# Ada.net
KiCad netlist of a schematic drawn in EasyEDA Pro
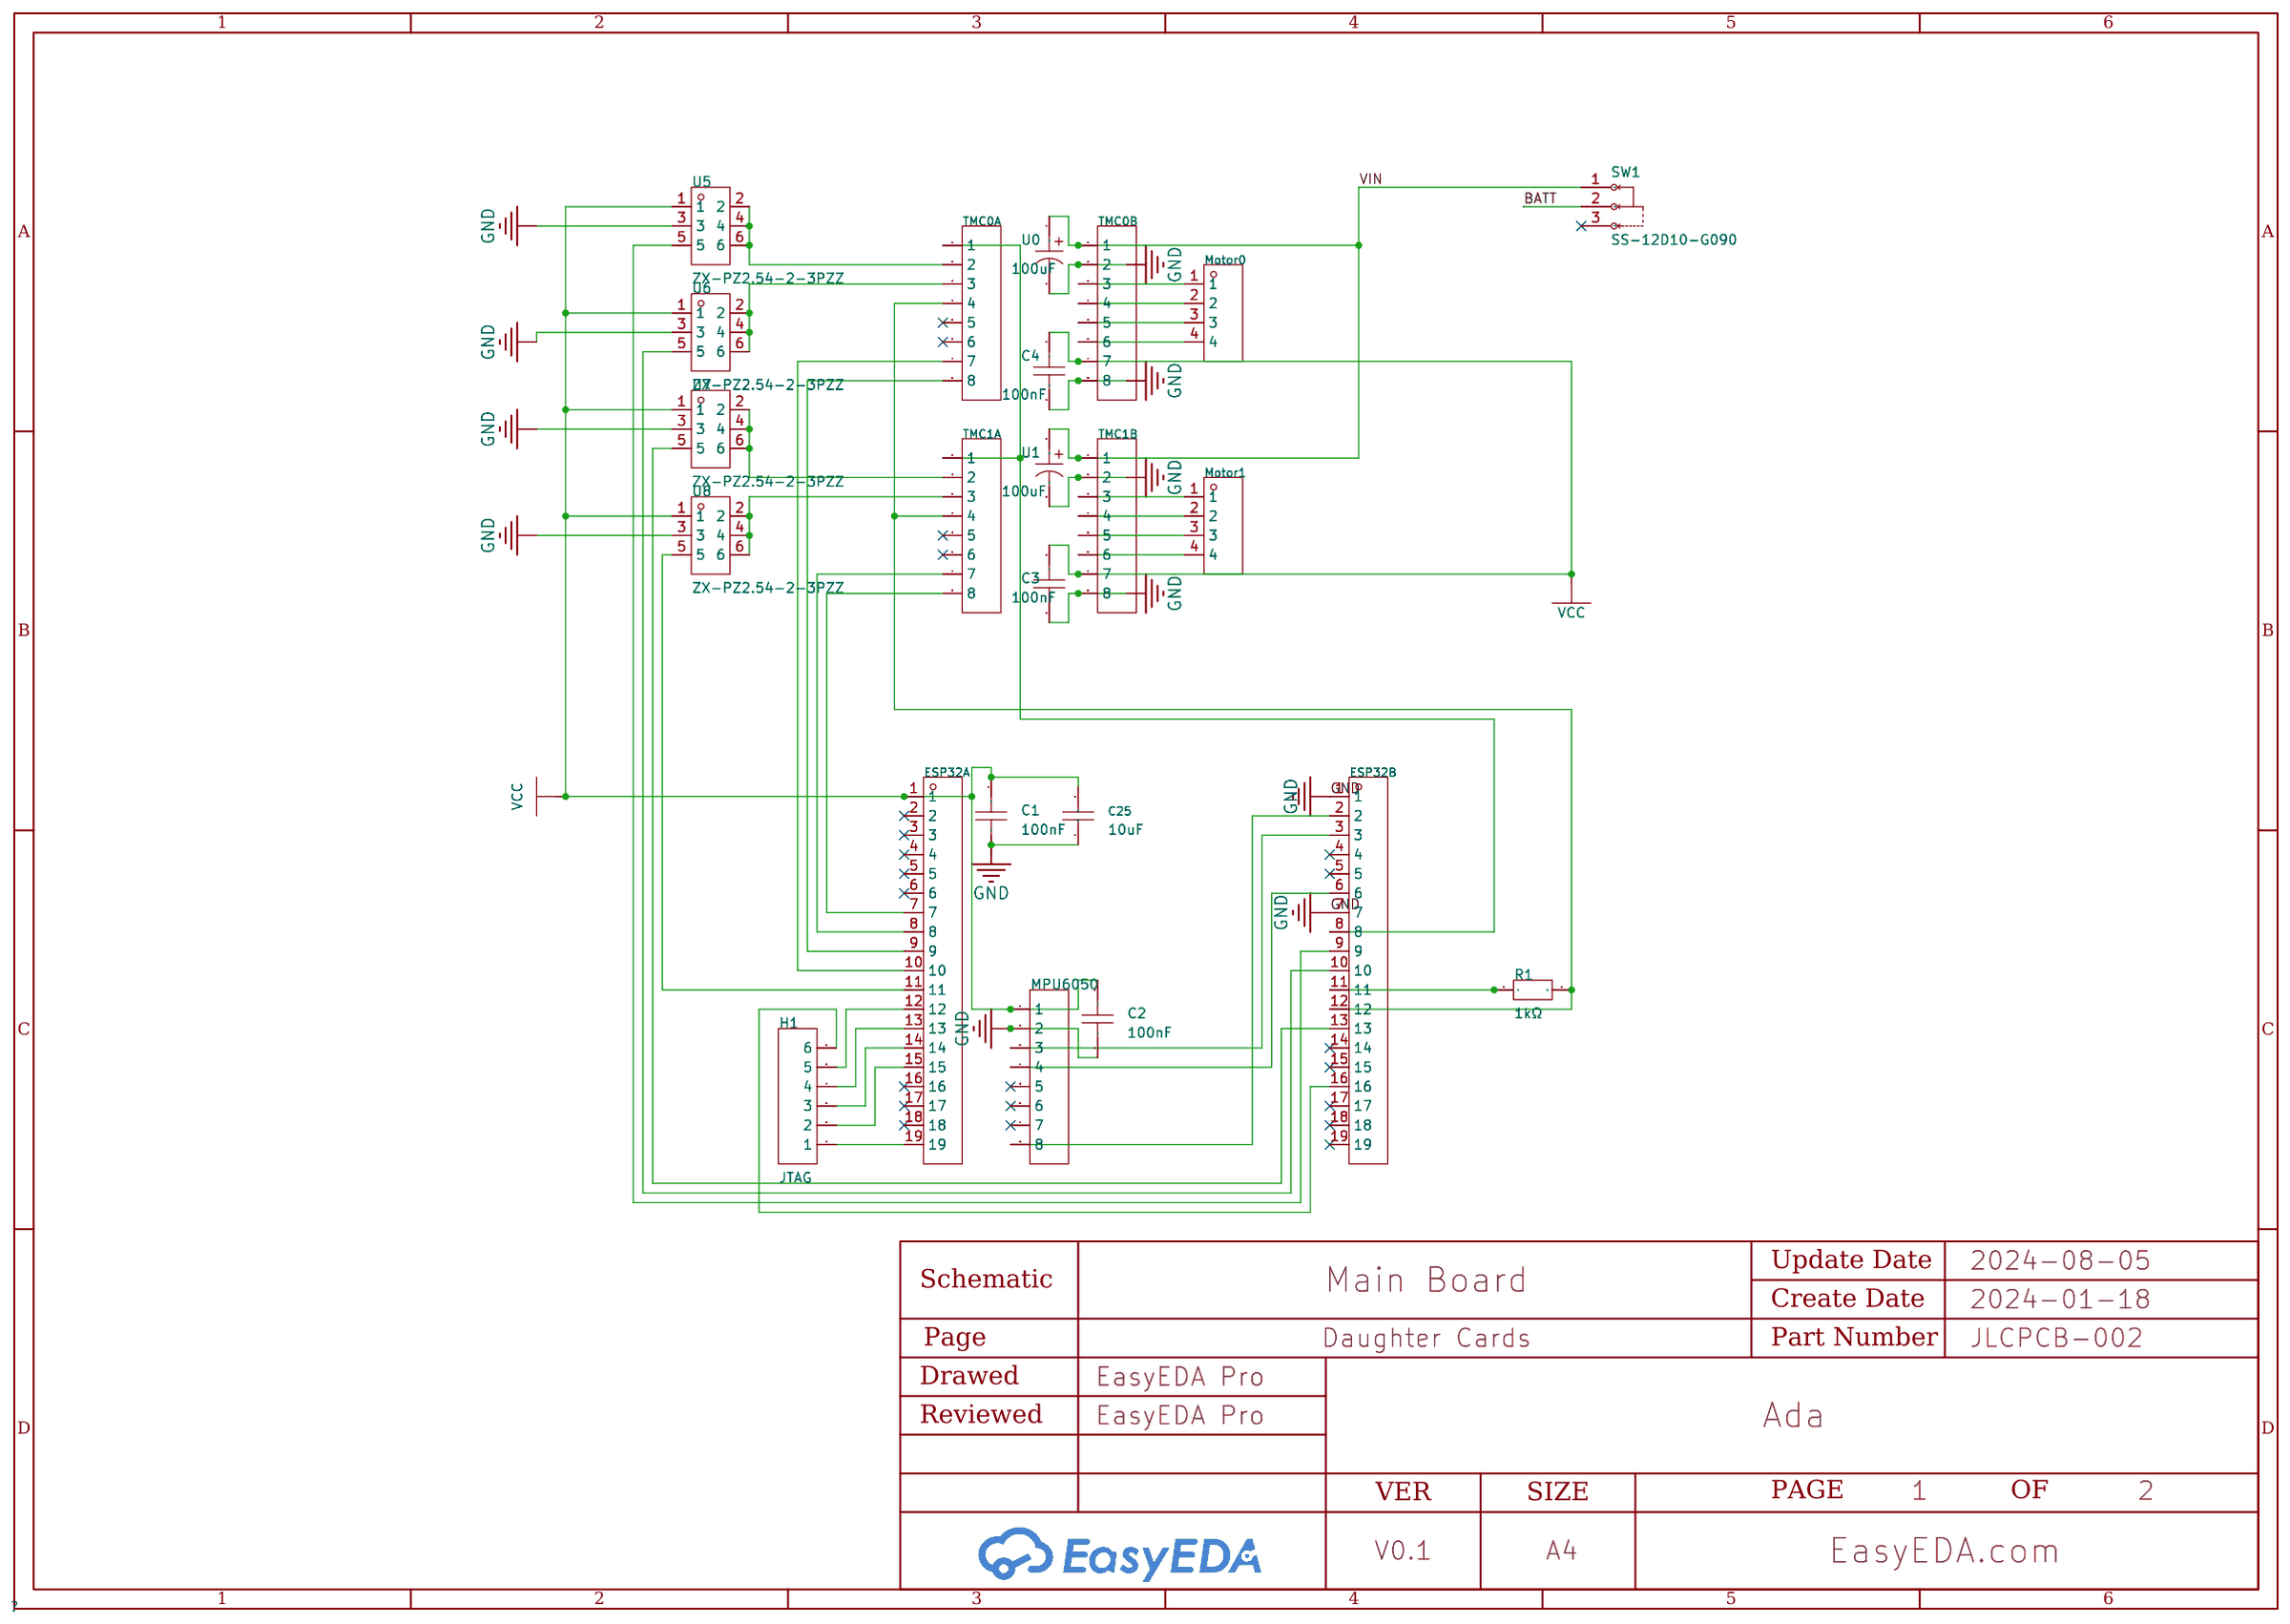
[diagram p0: Daughter Cards]
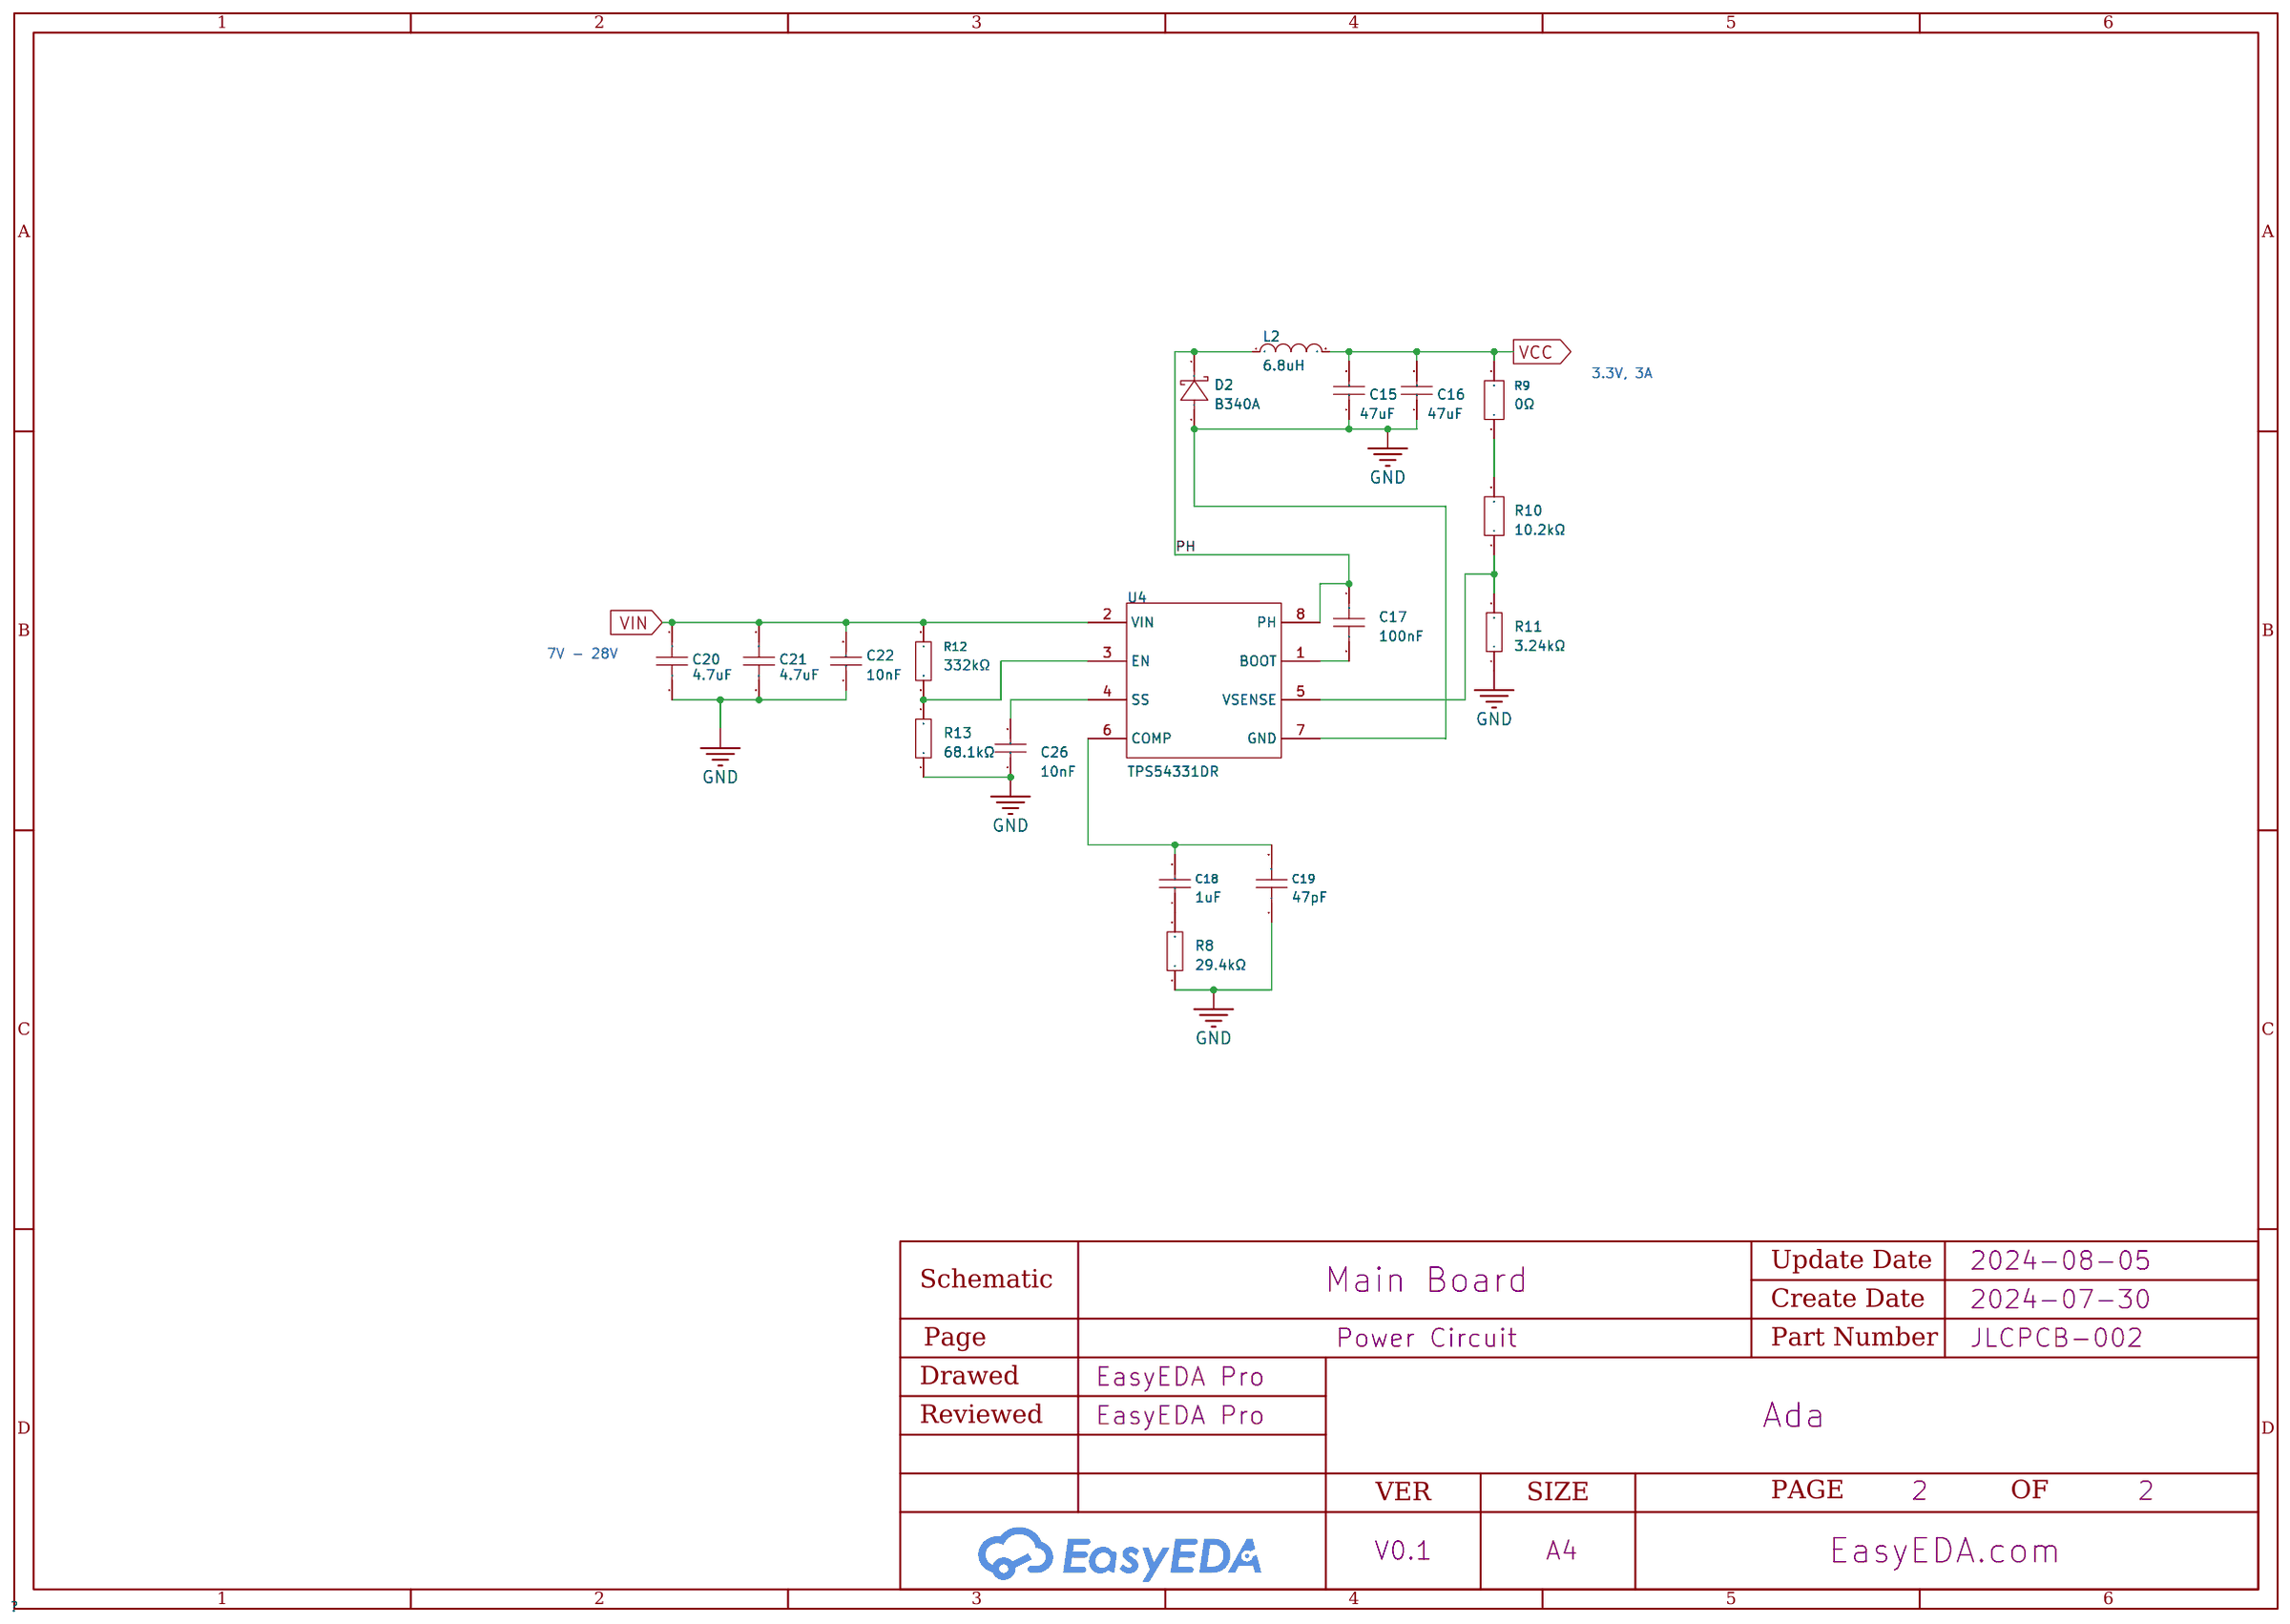
[diagram p1: Power Circuit]

(export (version "E")
  (design (tool "Eeschema 10.0.6"))
  (components
    (comp (ref "C1")
      (value "100nF")
      (footprint "easyedapro:C0201")
      (fields
        (field (name "Manufacturer Part") "CL03A104KQ3NNNC")
        (field (name "Manufacturer") "SAMSUNG(三星)")
      )
      (libsource (lib "easyedapro") (part "CL03A104KQ3NNNC"))
    )
    (comp (ref "C2")
      (value "100nF")
      (footprint "easyedapro:C0201")
      (fields
        (field (name "Manufacturer Part") "CL03A104KQ3NNNC")
        (field (name "Manufacturer") "SAMSUNG(三星)")
      )
      (libsource (lib "easyedapro") (part "CL03A104KQ3NNNC"))
    )
    (comp (ref "C3")
      (value "100nF")
      (footprint "easyedapro:C0201")
      (fields
        (field (name "Manufacturer Part") "CL03A104KQ3NNNC")
        (field (name "Manufacturer") "SAMSUNG(三星)")
      )
      (libsource (lib "easyedapro") (part "CL03A104KQ3NNNC"))
    )
    (comp (ref "C4")
      (value "100nF")
      (footprint "easyedapro:C0201")
      (fields
        (field (name "Manufacturer Part") "CL03A104KQ3NNNC")
        (field (name "Manufacturer") "SAMSUNG(三星)")
      )
      (libsource (lib "easyedapro") (part "CL03A104KQ3NNNC"))
    )
    (comp (ref "C25")
      (value "10uF")
      (footprint "easyedapro:C0402")
      (fields
        (field (name "Manufacturer Part") "CL05A106MQ5NUNC")
        (field (name "Manufacturer") "SAMSUNG(三星)")
      )
      (libsource (lib "easyedapro") (part "CL05A106MQ5NUNC"))
    )
    (comp (ref "ESP32A")
      (value "ESP32")
      (footprint "easyedapro:HDR-TH_19P-P2.54-V-F")
      (fields (field (name "Manufacturer Part") "2.54-1*19P母") (field (name "Manufacturer") "BOOMELE(博穆精密)"))
      (libsource (lib "easyedapro") (part "2.54-1*19P母"))
    )
    (comp (ref "ESP32B")
      (value "2.54-1*19P母")
      (footprint "easyedapro:HDR-TH_19P-P2.54-V-F")
      (fields (field (name "Manufacturer") "BOOMELE(博穆精密)"))
      (libsource (lib "easyedapro") (part "2.54-1*19P母"))
    )
    (comp (ref "H1")
      (value "JTAG")
      (footprint "easyedapro:HDR-TH_6P-P2.54-V-M-1")
      (fields (field (name "Manufacturer Part") "2.54-1x6P直针") (field (name "Manufacturer") "BOOMELE(博穆精密)"))
      (libsource (lib "easyedapro") (part "Header-Male-2.54_1x6"))
    )
    (comp (ref "Motor0")
      (value "Motor 0")
      (footprint "easyedapro:HDR-TH_4P-P2.54-V-M")
      (fields (field (name "Manufacturer Part") "PZ254V-11-04P") (field (name "Manufacturer") "XFCN(兴飞)"))
      (libsource (lib "easyedapro") (part "PZ254V-11-04P_C2691448"))
    )
    (comp (ref "Motor1")
      (value "Motor 1")
      (footprint "easyedapro:HDR-TH_4P-P2.54-V-M")
      (fields (field (name "Manufacturer Part") "PZ254V-11-04P") (field (name "Manufacturer") "XFCN(兴飞)"))
      (libsource (lib "easyedapro") (part "PZ254V-11-04P_C2691448"))
    )
    (comp (ref "MPU6050")
      (value "MPU6050")
      (footprint "easyedapro:HDR-TH_8P-P2.54-V-F-1")
      (fields (field (name "Manufacturer Part") "2.54-1*8P母环保") (field (name "Manufacturer") "BOOMELE(博穆精密)"))
      (libsource (lib "easyedapro") (part "Header-Female-2.54_1x8"))
    )
    (comp (ref "R1")
      (value "1kΩ")
      (footprint "easyedapro:R0603")
      (fields (field (name "Manufacturer Part") "FCR0603F1K") (field (name "Manufacturer") "VO(翔胜)"))
      (libsource (lib "easyedapro") (part "FCR0603F1K"))
    )
    (comp (ref "SW1")
      (value "SS-12D10-G090")
      (footprint "easyedapro:SW-TH_3P-L12.7-W6.6-P4.70_C9900034369")
      (fields (field (name "Manufacturer") "G-Switch(品赞)"))
      (libsource (lib "easyedapro") (part "SS-12D10-G090"))
    )
    (comp (ref "TMC0A")
      (value "TMC0A")
      (footprint "easyedapro:HDR-TH_8P-P2.54-V-F-1")
      (fields (field (name "Manufacturer Part") "2.54-1*8P母环保") (field (name "Manufacturer") "BOOMELE(博穆精密)"))
      (libsource (lib "easyedapro") (part "Header-Female-2.54_1x8"))
    )
    (comp (ref "TMC0B")
      (value "2.54-1*8P母环保")
      (footprint "easyedapro:HDR-TH_8P-P2.54-V-F-1")
      (fields (field (name "Manufacturer") "BOOMELE(博穆精密)"))
      (libsource (lib "easyedapro") (part "Header-Female-2.54_1x8"))
    )
    (comp (ref "TMC1A")
      (value "TMC2209")
      (footprint "easyedapro:HDR-TH_8P-P2.54-V-F-1")
      (fields (field (name "Manufacturer Part") "2.54-1*8P母环保") (field (name "Manufacturer") "BOOMELE(博穆精密)"))
      (libsource (lib "easyedapro") (part "Header-Female-2.54_1x8"))
    )
    (comp (ref "TMC1B")
      (value "2.54-1*8P母环保")
      (footprint "easyedapro:HDR-TH_8P-P2.54-V-F-1")
      (fields (field (name "Manufacturer") "BOOMELE(博穆精密)"))
      (libsource (lib "easyedapro") (part "Header-Female-2.54_1x8"))
    )
    (comp (ref "U0")
      (value "100uF")
      (footprint "easyedapro:CAP-TH_BD6.3-P2.50-D0.5-FD")
      (fields (field (name "Manufacturer Part") "03EC0728") (field (name "Manufacturer") "KNSCHA(科尼盛)"))
      (libsource (lib "easyedapro") (part "03EC0728"))
    )
    (comp (ref "U1")
      (value "100uF")
      (footprint "easyedapro:CAP-TH_BD6.3-P2.50-D0.5-FD")
      (fields (field (name "Manufacturer Part") "03EC0728") (field (name "Manufacturer") "KNSCHA(科尼盛)"))
      (libsource (lib "easyedapro") (part "03EC0728"))
    )
    (comp (ref "U5")
      (value "ZX-PZ2.54-2-3PZZ")
      (footprint "easyedapro:HDR-TH_6P-P2.54-V-M-R2-C3-S2.54-1")
      (fields (field (name "Manufacturer") "Megastar(兆星)"))
      (libsource (lib "easyedapro") (part "ZX-PZ2.54-2-3PZZ"))
    )
    (comp (ref "U6")
      (value "ZX-PZ2.54-2-3PZZ")
      (footprint "easyedapro:HDR-TH_6P-P2.54-V-M-R2-C3-S2.54-1")
      (fields (field (name "Manufacturer") "Megastar(兆星)"))
      (libsource (lib "easyedapro") (part "ZX-PZ2.54-2-3PZZ"))
    )
    (comp (ref "U7")
      (value "ZX-PZ2.54-2-3PZZ")
      (footprint "easyedapro:HDR-TH_6P-P2.54-V-M-R2-C3-S2.54-1")
      (fields (field (name "Manufacturer") "Megastar(兆星)"))
      (libsource (lib "easyedapro") (part "ZX-PZ2.54-2-3PZZ"))
    )
    (comp (ref "U8")
      (value "ZX-PZ2.54-2-3PZZ")
      (footprint "easyedapro:HDR-TH_6P-P2.54-V-M-R2-C3-S2.54-1")
      (fields (field (name "Manufacturer") "Megastar(兆星)"))
      (libsource (lib "easyedapro") (part "ZX-PZ2.54-2-3PZZ"))
    )
    (comp (ref "C15")
      (value "47uF")
      (footprint "easyedapro:C0805")
      (fields
        (field (name "Manufacturer Part") "CL21A476MQYNNNE")
        (field (name "Manufacturer") "SAMSUNG(三星)")
      )
      (libsource (lib "easyedapro") (part "CL21A476MQYNNNE"))
    )
    (comp (ref "C16")
      (value "47uF")
      (footprint "easyedapro:C0805")
      (fields
        (field (name "Manufacturer Part") "CL21A476MQYNNNE")
        (field (name "Manufacturer") "SAMSUNG(三星)")
      )
      (libsource (lib "easyedapro") (part "CL21A476MQYNNNE"))
    )
    (comp (ref "C17")
      (value "100nF")
      (footprint "easyedapro:C0201")
      (fields
        (field (name "Manufacturer Part") "CL03A104KQ3NNNC")
        (field (name "Manufacturer") "SAMSUNG(三星)")
      )
      (libsource (lib "easyedapro") (part "CL03A104KQ3NNNC"))
    )
    (comp (ref "C18")
      (value "1uF")
      (footprint "easyedapro:C0402")
      (fields
        (field (name "Manufacturer Part") "CL05A105KQ5NNNC")
        (field (name "Manufacturer") "SAMSUNG(三星)")
      )
      (libsource (lib "easyedapro") (part "CL05A105KQ5NNNC"))
    )
    (comp (ref "C19")
      (value "47pF")
      (footprint "easyedapro:C0603")
      (fields
        (field (name "Manufacturer Part") "CC0603JRNPO8BN470")
        (field (name "Manufacturer") "YAGEO(国巨)")
      )
      (libsource (lib "easyedapro") (part "CC0603JRNPO8BN470"))
    )
    (comp (ref "C20")
      (value "4.7uF")
      (footprint "easyedapro:C0603")
      (fields
        (field (name "Manufacturer Part") "CL10A475KL8NRNC")
        (field (name "Manufacturer") "SAMSUNG(三星)")
      )
      (libsource (lib "easyedapro") (part "CL10A475KL8NRNC"))
    )
    (comp (ref "C21")
      (value "4.7uF")
      (footprint "easyedapro:C0603")
      (fields
        (field (name "Manufacturer Part") "CL10A475KL8NRNC")
        (field (name "Manufacturer") "SAMSUNG(三星)")
      )
      (libsource (lib "easyedapro") (part "CL10A475KL8NRNC"))
    )
    (comp (ref "C22")
      (value "10nF")
      (footprint "easyedapro:C0603")
      (fields
        (field (name "Manufacturer Part") "CL10B103KB8NNNC")
        (field (name "Manufacturer") "SAMSUNG(三星)")
      )
      (libsource (lib "easyedapro") (part "CL10B103KB8NNNC"))
    )
    (comp (ref "C26")
      (value "10nF")
      (footprint "easyedapro:C0201")
      (fields
        (field (name "Manufacturer Part") "GRM033R70J103KA01D")
        (field (name "Manufacturer") "muRata(村田)")
      )
      (libsource (lib "easyedapro") (part "GRM033R70J103KA01D"))
    )
    (comp (ref "D2")
      (value "B340A")
      (footprint "easyedapro:SMA_L4.3-W2.6-LS5.0-RD")
      (fields (field (name "Manufacturer") "FUXINSEMI(富芯森美)"))
      (libsource (lib "easyedapro") (part "B340A_C3018525"))
    )
    (comp (ref "L2")
      (value "6.8uH")
      (footprint "easyedapro:IND-SMD_L5.2-W5.2_MS0530-XX")
      (fields (field (name "Manufacturer Part") "MDA5030-6R8M") (field (name "Manufacturer") "KOHERelec(科或)"))
      (libsource (lib "easyedapro") (part "MDA5030-6R8M"))
    )
    (comp (ref "R8")
      (value "29.4kΩ")
      (footprint "easyedapro:R0201")
      (fields (field (name "Manufacturer Part") "RC-01W2942FT") (field (name "Manufacturer") "FH(风华)"))
      (libsource (lib "easyedapro") (part "RC-01W2942FT"))
    )
    (comp (ref "R9")
      (value "0Ω")
      (footprint "easyedapro:R0201")
      (fields
        (field (name "Manufacturer Part") "0201WMF0000TEE")
        (field (name "Manufacturer") "UNI-ROYAL(厚声)")
      )
      (libsource (lib "easyedapro") (part "0201WMF0000TEE"))
    )
    (comp (ref "R10")
      (value "10.2kΩ")
      (footprint "easyedapro:R0201")
      (fields (field (name "Manufacturer Part") "RTT011022FTH") (field (name "Manufacturer") "RALEC(旺诠)"))
      (libsource (lib "easyedapro") (part "RTT011022FTH"))
    )
    (comp (ref "R11")
      (value "3.24kΩ")
      (footprint "easyedapro:R0603")
      (fields
        (field (name "Manufacturer Part") "0603WAF3241T5E")
        (field (name "Manufacturer") "UNI-ROYAL(厚声)")
      )
      (libsource (lib "easyedapro") (part "0603WAF3241T5E"))
    )
    (comp (ref "R12")
      (value "332kΩ")
      (footprint "easyedapro:R0402")
      (fields
        (field (name "Manufacturer Part") "0402WGF3323TCE")
        (field (name "Manufacturer") "UNI-ROYAL(厚声)")
      )
      (libsource (lib "easyedapro") (part "0402WGF3323TCE"))
    )
    (comp (ref "R13")
      (value "68.1kΩ")
      (footprint "easyedapro:R0402")
      (fields (field (name "Manufacturer Part") "AC0402FR-0768K1L") (field (name "Manufacturer") "YAGEO(国巨)"))
      (libsource (lib "easyedapro") (part "AC0402FR-0768K1L"))
    )
    (comp (ref "U4")
      (value "TPS54331DR")
      (footprint "easyedapro:SOIC-8_L5.0-W4.0-P1.27-LS6.0-BL")
      (fields (field (name "Manufacturer") "TI(德州仪器)"))
      (libsource (lib "easyedapro") (part "TPS54331DR"))
    )
  )
  (nets
    (net (code "1") (name "BATT") (class "Default")
      (node (ref "SW1") (pin "2") (pinfunction "2_2") (pintype "unspecified"))
    )
    (net (code "2") (name "GND") (class "Default")
      (node (ref "C1") (pin "2") (pinfunction "2_2") (pintype "unspecified"))
      (node (ref "C15") (pin "1") (pinfunction "1_1") (pintype "input"))
      (node (ref "C16") (pin "1") (pinfunction "1_1") (pintype "input"))
      (node (ref "C19") (pin "1") (pinfunction "1_1") (pintype "input"))
      (node (ref "C2") (pin "2") (pinfunction "2_2") (pintype "unspecified"))
      (node (ref "C20") (pin "2") (pinfunction "2_2") (pintype "unspecified"))
      (node (ref "C21") (pin "2") (pinfunction "2_2") (pintype "unspecified"))
      (node (ref "C22") (pin "1") (pinfunction "1_1") (pintype "input"))
      (node (ref "C25") (pin "1") (pinfunction "1_1") (pintype "input"))
      (node (ref "C26") (pin "1") (pinfunction "1_1") (pintype "input"))
      (node (ref "C3") (pin "2") (pinfunction "2_2") (pintype "unspecified"))
      (node (ref "C4") (pin "2") (pinfunction "2_2") (pintype "unspecified"))
      (node (ref "D2") (pin "2") (pinfunction "A_2") (pintype "unspecified"))
      (node (ref "ESP32B") (pin "1") (pinfunction "1_1") (pintype "input"))
      (node (ref "ESP32B") (pin "7") (pinfunction "7_7") (pintype "input"))
      (node (ref "MPU6050") (pin "2") (pinfunction "2_2") (pintype "input"))
      (node (ref "R11") (pin "1") (pinfunction "1_1") (pintype "input"))
      (node (ref "R13") (pin "1") (pinfunction "1_1") (pintype "unspecified"))
      (node (ref "R8") (pin "1") (pinfunction "1_1") (pintype "unspecified"))
      (node (ref "TMC0B") (pin "2") (pinfunction "2_2") (pintype "input"))
      (node (ref "TMC0B") (pin "8") (pinfunction "8_8") (pintype "input"))
      (node (ref "TMC1B") (pin "2") (pinfunction "2_2") (pintype "input"))
      (node (ref "TMC1B") (pin "8") (pinfunction "8_8") (pintype "input"))
      (node (ref "U0") (pin "2") (pinfunction "2_2") (pintype "input"))
      (node (ref "U1") (pin "2") (pinfunction "2_2") (pintype "input"))
      (node (ref "U4") (pin "7") (pinfunction "GND_7") (pintype "unspecified"))
      (node (ref "U5") (pin "3") (pinfunction "3_3") (pintype "unspecified"))
      (node (ref "U6") (pin "3") (pinfunction "3_3") (pintype "unspecified"))
      (node (ref "U7") (pin "3") (pinfunction "3_3") (pintype "unspecified"))
      (node (ref "U8") (pin "3") (pinfunction "3_3") (pintype "unspecified"))
    )
    (net (code "3") (name "Net-(C18-Pad1)") (class "Default")
      (node (ref "C18") (pin "1") (pinfunction "1_1") (pintype "input"))
      (node (ref "R8") (pin "2") (pinfunction "2_2") (pintype "unspecified"))
    )
    (net (code "4") (name "Net-(ESP32A-Pad7)") (class "Default")
      (node (ref "ESP32A") (pin "7") (pinfunction "7_7") (pintype "input"))
      (node (ref "TMC1A") (pin "8") (pinfunction "8_8") (pintype "input"))
    )
    (net (code "5") (name "Net-(ESP32A-Pad8)") (class "Default")
      (node (ref "ESP32A") (pin "8") (pinfunction "8_8") (pintype "input"))
      (node (ref "TMC1A") (pin "7") (pinfunction "7_7") (pintype "input"))
    )
    (net (code "6") (name "Net-(ESP32A-Pad9)") (class "Default")
      (node (ref "ESP32A") (pin "9") (pinfunction "9_9") (pintype "input"))
      (node (ref "TMC0A") (pin "8") (pinfunction "8_8") (pintype "input"))
    )
    (net (code "7") (name "Net-(ESP32A-Pad10)") (class "Default")
      (node (ref "ESP32A") (pin "10") (pinfunction "10_10") (pintype "input"))
      (node (ref "TMC0A") (pin "7") (pinfunction "7_7") (pintype "input"))
    )
    (net (code "8") (name "Net-(ESP32A-Pad11)") (class "Default")
      (node (ref "ESP32A") (pin "11") (pinfunction "11_11") (pintype "input"))
      (node (ref "U8") (pin "5") (pinfunction "5_5") (pintype "unspecified"))
    )
    (net (code "9") (name "Net-(ESP32A-Pad12)") (class "Default")
      (node (ref "ESP32A") (pin "12") (pinfunction "12_12") (pintype "input"))
      (node (ref "H1") (pin "5") (pinfunction "5_5") (pintype "input"))
    )
    (net (code "10") (name "Net-(ESP32A-Pad13)") (class "Default")
      (node (ref "ESP32A") (pin "13") (pinfunction "13_13") (pintype "input"))
      (node (ref "H1") (pin "4") (pinfunction "4_4") (pintype "input"))
    )
    (net (code "11") (name "Net-(ESP32A-Pad14)") (class "Default")
      (node (ref "ESP32A") (pin "14") (pinfunction "14_14") (pintype "input"))
      (node (ref "H1") (pin "3") (pinfunction "3_3") (pintype "input"))
    )
    (net (code "12") (name "Net-(ESP32A-Pad15)") (class "Default")
      (node (ref "ESP32A") (pin "15") (pinfunction "15_15") (pintype "input"))
      (node (ref "H1") (pin "2") (pinfunction "2_2") (pintype "input"))
    )
    (net (code "13") (name "Net-(ESP32A-Pad19)") (class "Default")
      (node (ref "ESP32A") (pin "19") (pinfunction "19_19") (pintype "input"))
      (node (ref "H1") (pin "1") (pinfunction "1_1") (pintype "input"))
    )
    (net (code "14") (name "Net-(ESP32B-Pad2)") (class "Default")
      (node (ref "ESP32B") (pin "2") (pinfunction "2_2") (pintype "input"))
      (node (ref "MPU6050") (pin "8") (pinfunction "8_8") (pintype "input"))
    )
    (net (code "15") (name "Net-(ESP32B-Pad3)") (class "Default")
      (node (ref "ESP32B") (pin "3") (pinfunction "3_3") (pintype "input"))
      (node (ref "MPU6050") (pin "3") (pinfunction "3_3") (pintype "input"))
    )
    (net (code "16") (name "Net-(ESP32B-Pad6)") (class "Default")
      (node (ref "ESP32B") (pin "6") (pinfunction "6_6") (pintype "input"))
      (node (ref "MPU6050") (pin "4") (pinfunction "4_4") (pintype "input"))
    )
    (net (code "17") (name "Net-(ESP32B-Pad8)") (class "Default")
      (node (ref "ESP32B") (pin "8") (pinfunction "8_8") (pintype "input"))
      (node (ref "TMC0A") (pin "1") (pinfunction "1_1") (pintype "input"))
      (node (ref "TMC1A") (pin "1") (pinfunction "1_1") (pintype "input"))
    )
    (net (code "18") (name "Net-(ESP32B-Pad9)") (class "Default")
      (node (ref "ESP32B") (pin "9") (pinfunction "9_9") (pintype "input"))
      (node (ref "U5") (pin "5") (pinfunction "5_5") (pintype "unspecified"))
    )
    (net (code "19") (name "Net-(ESP32B-Pad10)") (class "Default")
      (node (ref "ESP32B") (pin "10") (pinfunction "10_10") (pintype "input"))
      (node (ref "U6") (pin "5") (pinfunction "5_5") (pintype "unspecified"))
    )
    (net (code "20") (name "Net-(ESP32B-Pad11)") (class "Default")
      (node (ref "ESP32B") (pin "11") (pinfunction "11_11") (pintype "input"))
      (node (ref "R1") (pin "1") (pinfunction "1_1") (pintype "unspecified"))
    )
    (net (code "21") (name "Net-(ESP32B-Pad12)") (class "Default")
      (node (ref "ESP32B") (pin "12") (pinfunction "12_12") (pintype "input"))
      (node (ref "R1") (pin "2") (pinfunction "2_2") (pintype "unspecified"))
      (node (ref "TMC0A") (pin "4") (pinfunction "4_4") (pintype "input"))
      (node (ref "TMC1A") (pin "4") (pinfunction "4_4") (pintype "input"))
    )
    (net (code "22") (name "Net-(ESP32B-Pad13)") (class "Default")
      (node (ref "ESP32B") (pin "13") (pinfunction "13_13") (pintype "input"))
      (node (ref "U7") (pin "5") (pinfunction "5_5") (pintype "unspecified"))
    )
    (net (code "23") (name "Net-(ESP32B-Pad16)") (class "Default")
      (node (ref "ESP32B") (pin "16") (pinfunction "16_16") (pintype "input"))
      (node (ref "H1") (pin "6") (pinfunction "6_6") (pintype "input"))
    )
    (net (code "24") (name "Net-(Motor0-Pad1)") (class "Default")
      (node (ref "Motor0") (pin "1") (pinfunction "1_1") (pintype "input"))
      (node (ref "TMC0B") (pin "3") (pinfunction "3_3") (pintype "input"))
    )
    (net (code "25") (name "Net-(Motor0-Pad2)") (class "Default")
      (node (ref "Motor0") (pin "2") (pinfunction "2_2") (pintype "input"))
      (node (ref "TMC0B") (pin "4") (pinfunction "4_4") (pintype "input"))
    )
    (net (code "26") (name "Net-(Motor0-Pad3)") (class "Default")
      (node (ref "Motor0") (pin "3") (pinfunction "3_3") (pintype "input"))
      (node (ref "TMC0B") (pin "5") (pinfunction "5_5") (pintype "input"))
    )
    (net (code "27") (name "Net-(Motor0-Pad4)") (class "Default")
      (node (ref "Motor0") (pin "4") (pinfunction "4_4") (pintype "input"))
      (node (ref "TMC0B") (pin "6") (pinfunction "6_6") (pintype "input"))
    )
    (net (code "28") (name "Net-(Motor1-Pad1)") (class "Default")
      (node (ref "Motor1") (pin "1") (pinfunction "1_1") (pintype "input"))
      (node (ref "TMC1B") (pin "3") (pinfunction "3_3") (pintype "input"))
    )
    (net (code "29") (name "Net-(Motor1-Pad2)") (class "Default")
      (node (ref "Motor1") (pin "2") (pinfunction "2_2") (pintype "input"))
      (node (ref "TMC1B") (pin "4") (pinfunction "4_4") (pintype "input"))
    )
    (net (code "30") (name "Net-(Motor1-Pad3)") (class "Default")
      (node (ref "Motor1") (pin "3") (pinfunction "3_3") (pintype "input"))
      (node (ref "TMC1B") (pin "5") (pinfunction "5_5") (pintype "input"))
    )
    (net (code "31") (name "Net-(Motor1-Pad4)") (class "Default")
      (node (ref "Motor1") (pin "4") (pinfunction "4_4") (pintype "input"))
      (node (ref "TMC1B") (pin "6") (pinfunction "6_6") (pintype "input"))
    )
    (net (code "32") (name "Net-(R10-Pad2)") (class "Default")
      (node (ref "R10") (pin "2") (pinfunction "2_2") (pintype "unspecified"))
      (node (ref "R9") (pin "1") (pinfunction "1_1") (pintype "input"))
    )
    (net (code "33") (name "Net-(TMC0A-Pad2)") (class "Default")
      (node (ref "TMC0A") (pin "2") (pinfunction "2_2") (pintype "input"))
      (node (ref "U5") (pin "2") (pinfunction "2_2") (pintype "unspecified"))
      (node (ref "U5") (pin "4") (pinfunction "4_4") (pintype "unspecified"))
      (node (ref "U5") (pin "6") (pinfunction "6_6") (pintype "unspecified"))
    )
    (net (code "34") (name "Net-(TMC0A-Pad3)") (class "Default")
      (node (ref "TMC0A") (pin "3") (pinfunction "3_3") (pintype "input"))
      (node (ref "U6") (pin "2") (pinfunction "2_2") (pintype "unspecified"))
      (node (ref "U6") (pin "4") (pinfunction "4_4") (pintype "unspecified"))
      (node (ref "U6") (pin "6") (pinfunction "6_6") (pintype "unspecified"))
    )
    (net (code "35") (name "Net-(TMC1A-Pad2)") (class "Default")
      (node (ref "TMC1A") (pin "2") (pinfunction "2_2") (pintype "input"))
      (node (ref "U7") (pin "2") (pinfunction "2_2") (pintype "unspecified"))
      (node (ref "U7") (pin "4") (pinfunction "4_4") (pintype "unspecified"))
      (node (ref "U7") (pin "6") (pinfunction "6_6") (pintype "unspecified"))
    )
    (net (code "36") (name "Net-(TMC1A-Pad3)") (class "Default")
      (node (ref "TMC1A") (pin "3") (pinfunction "3_3") (pintype "input"))
      (node (ref "U8") (pin "2") (pinfunction "2_2") (pintype "unspecified"))
      (node (ref "U8") (pin "4") (pinfunction "4_4") (pintype "unspecified"))
      (node (ref "U8") (pin "6") (pinfunction "6_6") (pintype "unspecified"))
    )
    (net (code "37") (name "Net-(U4-BOOT)") (class "Default")
      (node (ref "C17") (pin "2") (pinfunction "2_2") (pintype "unspecified"))
      (node (ref "U4") (pin "1") (pinfunction "BOOT_1") (pintype "unspecified"))
    )
    (net (code "38") (name "Net-(U4-COMP)") (class "Default")
      (node (ref "C18") (pin "2") (pinfunction "2_2") (pintype "input"))
      (node (ref "C19") (pin "2") (pinfunction "2_2") (pintype "input"))
      (node (ref "U4") (pin "6") (pinfunction "COMP_6") (pintype "unspecified"))
    )
    (net (code "39") (name "Net-(U4-EN)") (class "Default")
      (node (ref "R12") (pin "1") (pinfunction "1_1") (pintype "input"))
      (node (ref "R13") (pin "2") (pinfunction "2_2") (pintype "unspecified"))
      (node (ref "U4") (pin "3") (pinfunction "EN_3") (pintype "unspecified"))
    )
    (net (code "40") (name "Net-(U4-SS)") (class "Default")
      (node (ref "C26") (pin "2") (pinfunction "2_2") (pintype "input"))
      (node (ref "U4") (pin "4") (pinfunction "SS_4") (pintype "unspecified"))
    )
    (net (code "41") (name "Net-(U4-VSENSE)") (class "Default")
      (node (ref "R10") (pin "1") (pinfunction "1_1") (pintype "unspecified"))
      (node (ref "R11") (pin "2") (pinfunction "2_2") (pintype "input"))
      (node (ref "U4") (pin "5") (pinfunction "VSENSE_5") (pintype "unspecified"))
    )
    (net (code "42") (name "PH") (class "Default")
      (node (ref "C17") (pin "1") (pinfunction "1_1") (pintype "unspecified"))
      (node (ref "D2") (pin "1") (pinfunction "K_1") (pintype "unspecified"))
      (node (ref "L2") (pin "1") (pinfunction "1_1") (pintype "unspecified"))
      (node (ref "U4") (pin "8") (pinfunction "PH_8") (pintype "unspecified"))
    )
    (net (code "43") (name "VCC") (class "Default")
      (node (ref "C1") (pin "1") (pinfunction "1_1") (pintype "unspecified"))
      (node (ref "C15") (pin "2") (pinfunction "2_2") (pintype "input"))
      (node (ref "C16") (pin "2") (pinfunction "2_2") (pintype "input"))
      (node (ref "C2") (pin "1") (pinfunction "1_1") (pintype "unspecified"))
      (node (ref "C25") (pin "2") (pinfunction "2_2") (pintype "input"))
      (node (ref "C3") (pin "1") (pinfunction "1_1") (pintype "unspecified"))
      (node (ref "C4") (pin "1") (pinfunction "1_1") (pintype "unspecified"))
      (node (ref "ESP32A") (pin "1") (pinfunction "1_1") (pintype "input"))
      (node (ref "L2") (pin "2") (pinfunction "2_2") (pintype "unspecified"))
      (node (ref "MPU6050") (pin "1") (pinfunction "1_1") (pintype "input"))
      (node (ref "R9") (pin "2") (pinfunction "2_2") (pintype "input"))
      (node (ref "TMC0B") (pin "7") (pinfunction "7_7") (pintype "input"))
      (node (ref "TMC1B") (pin "7") (pinfunction "7_7") (pintype "input"))
      (node (ref "U5") (pin "1") (pinfunction "1_1") (pintype "unspecified"))
      (node (ref "U6") (pin "1") (pinfunction "1_1") (pintype "unspecified"))
      (node (ref "U7") (pin "1") (pinfunction "1_1") (pintype "unspecified"))
      (node (ref "U8") (pin "1") (pinfunction "1_1") (pintype "unspecified"))
    )
    (net (code "44") (name "VIN") (class "Default")
      (node (ref "C20") (pin "1") (pinfunction "1_1") (pintype "unspecified"))
      (node (ref "C21") (pin "1") (pinfunction "1_1") (pintype "unspecified"))
      (node (ref "C22") (pin "2") (pinfunction "2_2") (pintype "input"))
      (node (ref "R12") (pin "2") (pinfunction "2_2") (pintype "input"))
      (node (ref "SW1") (pin "1") (pinfunction "1_1") (pintype "unspecified"))
      (node (ref "TMC0B") (pin "1") (pinfunction "1_1") (pintype "input"))
      (node (ref "TMC1B") (pin "1") (pinfunction "1_1") (pintype "input"))
      (node (ref "U0") (pin "1") (pinfunction "1_1") (pintype "input"))
      (node (ref "U1") (pin "1") (pinfunction "1_1") (pintype "input"))
      (node (ref "U4") (pin "2") (pinfunction "VIN_2") (pintype "unspecified"))
    )
    (net (code "45") (name "unconnected-(ESP32A-Pad2)") (class "Default")
      (node (ref "ESP32A") (pin "2") (pinfunction "2_2") (pintype "input+no_connect"))
    )
    (net (code "46") (name "unconnected-(ESP32A-Pad3)") (class "Default")
      (node (ref "ESP32A") (pin "3") (pinfunction "3_3") (pintype "input+no_connect"))
    )
    (net (code "47") (name "unconnected-(ESP32A-Pad4)") (class "Default")
      (node (ref "ESP32A") (pin "4") (pinfunction "4_4") (pintype "input+no_connect"))
    )
    (net (code "48") (name "unconnected-(ESP32A-Pad5)") (class "Default")
      (node (ref "ESP32A") (pin "5") (pinfunction "5_5") (pintype "input+no_connect"))
    )
    (net (code "49") (name "unconnected-(ESP32A-Pad6)") (class "Default")
      (node (ref "ESP32A") (pin "6") (pinfunction "6_6") (pintype "input+no_connect"))
    )
    (net (code "50") (name "unconnected-(ESP32A-Pad16)") (class "Default")
      (node (ref "ESP32A") (pin "16") (pinfunction "16_16") (pintype "input+no_connect"))
    )
    (net (code "51") (name "unconnected-(ESP32A-Pad17)") (class "Default")
      (node (ref "ESP32A") (pin "17") (pinfunction "17_17") (pintype "input+no_connect"))
    )
    (net (code "52") (name "unconnected-(ESP32A-Pad18)") (class "Default")
      (node (ref "ESP32A") (pin "18") (pinfunction "18_18") (pintype "input+no_connect"))
    )
    (net (code "53") (name "unconnected-(ESP32B-Pad4)") (class "Default")
      (node (ref "ESP32B") (pin "4") (pinfunction "4_4") (pintype "input+no_connect"))
    )
    (net (code "54") (name "unconnected-(ESP32B-Pad5)") (class "Default")
      (node (ref "ESP32B") (pin "5") (pinfunction "5_5") (pintype "input+no_connect"))
    )
    (net (code "55") (name "unconnected-(ESP32B-Pad14)") (class "Default")
      (node (ref "ESP32B") (pin "14") (pinfunction "14_14") (pintype "input+no_connect"))
    )
    (net (code "56") (name "unconnected-(ESP32B-Pad15)") (class "Default")
      (node (ref "ESP32B") (pin "15") (pinfunction "15_15") (pintype "input+no_connect"))
    )
    (net (code "57") (name "unconnected-(ESP32B-Pad17)") (class "Default")
      (node (ref "ESP32B") (pin "17") (pinfunction "17_17") (pintype "input+no_connect"))
    )
    (net (code "58") (name "unconnected-(ESP32B-Pad18)") (class "Default")
      (node (ref "ESP32B") (pin "18") (pinfunction "18_18") (pintype "input+no_connect"))
    )
    (net (code "59") (name "unconnected-(ESP32B-Pad19)") (class "Default")
      (node (ref "ESP32B") (pin "19") (pinfunction "19_19") (pintype "input+no_connect"))
    )
    (net (code "60") (name "unconnected-(MPU6050-Pad5)") (class "Default")
      (node (ref "MPU6050") (pin "5") (pinfunction "5_5") (pintype "input+no_connect"))
    )
    (net (code "61") (name "unconnected-(MPU6050-Pad6)") (class "Default")
      (node (ref "MPU6050") (pin "6") (pinfunction "6_6") (pintype "input+no_connect"))
    )
    (net (code "62") (name "unconnected-(MPU6050-Pad7)") (class "Default")
      (node (ref "MPU6050") (pin "7") (pinfunction "7_7") (pintype "input+no_connect"))
    )
    (net (code "63") (name "unconnected-(SW1-Pad3)") (class "Default")
      (node (ref "SW1") (pin "3") (pinfunction "3_3") (pintype "unspecified+no_connect"))
    )
    (net (code "64") (name "unconnected-(TMC0A-Pad5)") (class "Default")
      (node (ref "TMC0A") (pin "5") (pinfunction "5_5") (pintype "input+no_connect"))
    )
    (net (code "65") (name "unconnected-(TMC0A-Pad6)") (class "Default")
      (node (ref "TMC0A") (pin "6") (pinfunction "6_6") (pintype "input+no_connect"))
    )
    (net (code "66") (name "unconnected-(TMC1A-Pad5)") (class "Default")
      (node (ref "TMC1A") (pin "5") (pinfunction "5_5") (pintype "input+no_connect"))
    )
    (net (code "67") (name "unconnected-(TMC1A-Pad6)") (class "Default")
      (node (ref "TMC1A") (pin "6") (pinfunction "6_6") (pintype "input+no_connect"))
    )
  )
)
